# 6coils-1-discrete.net
KiCad netlist of a schematic drawn in EasyEDA
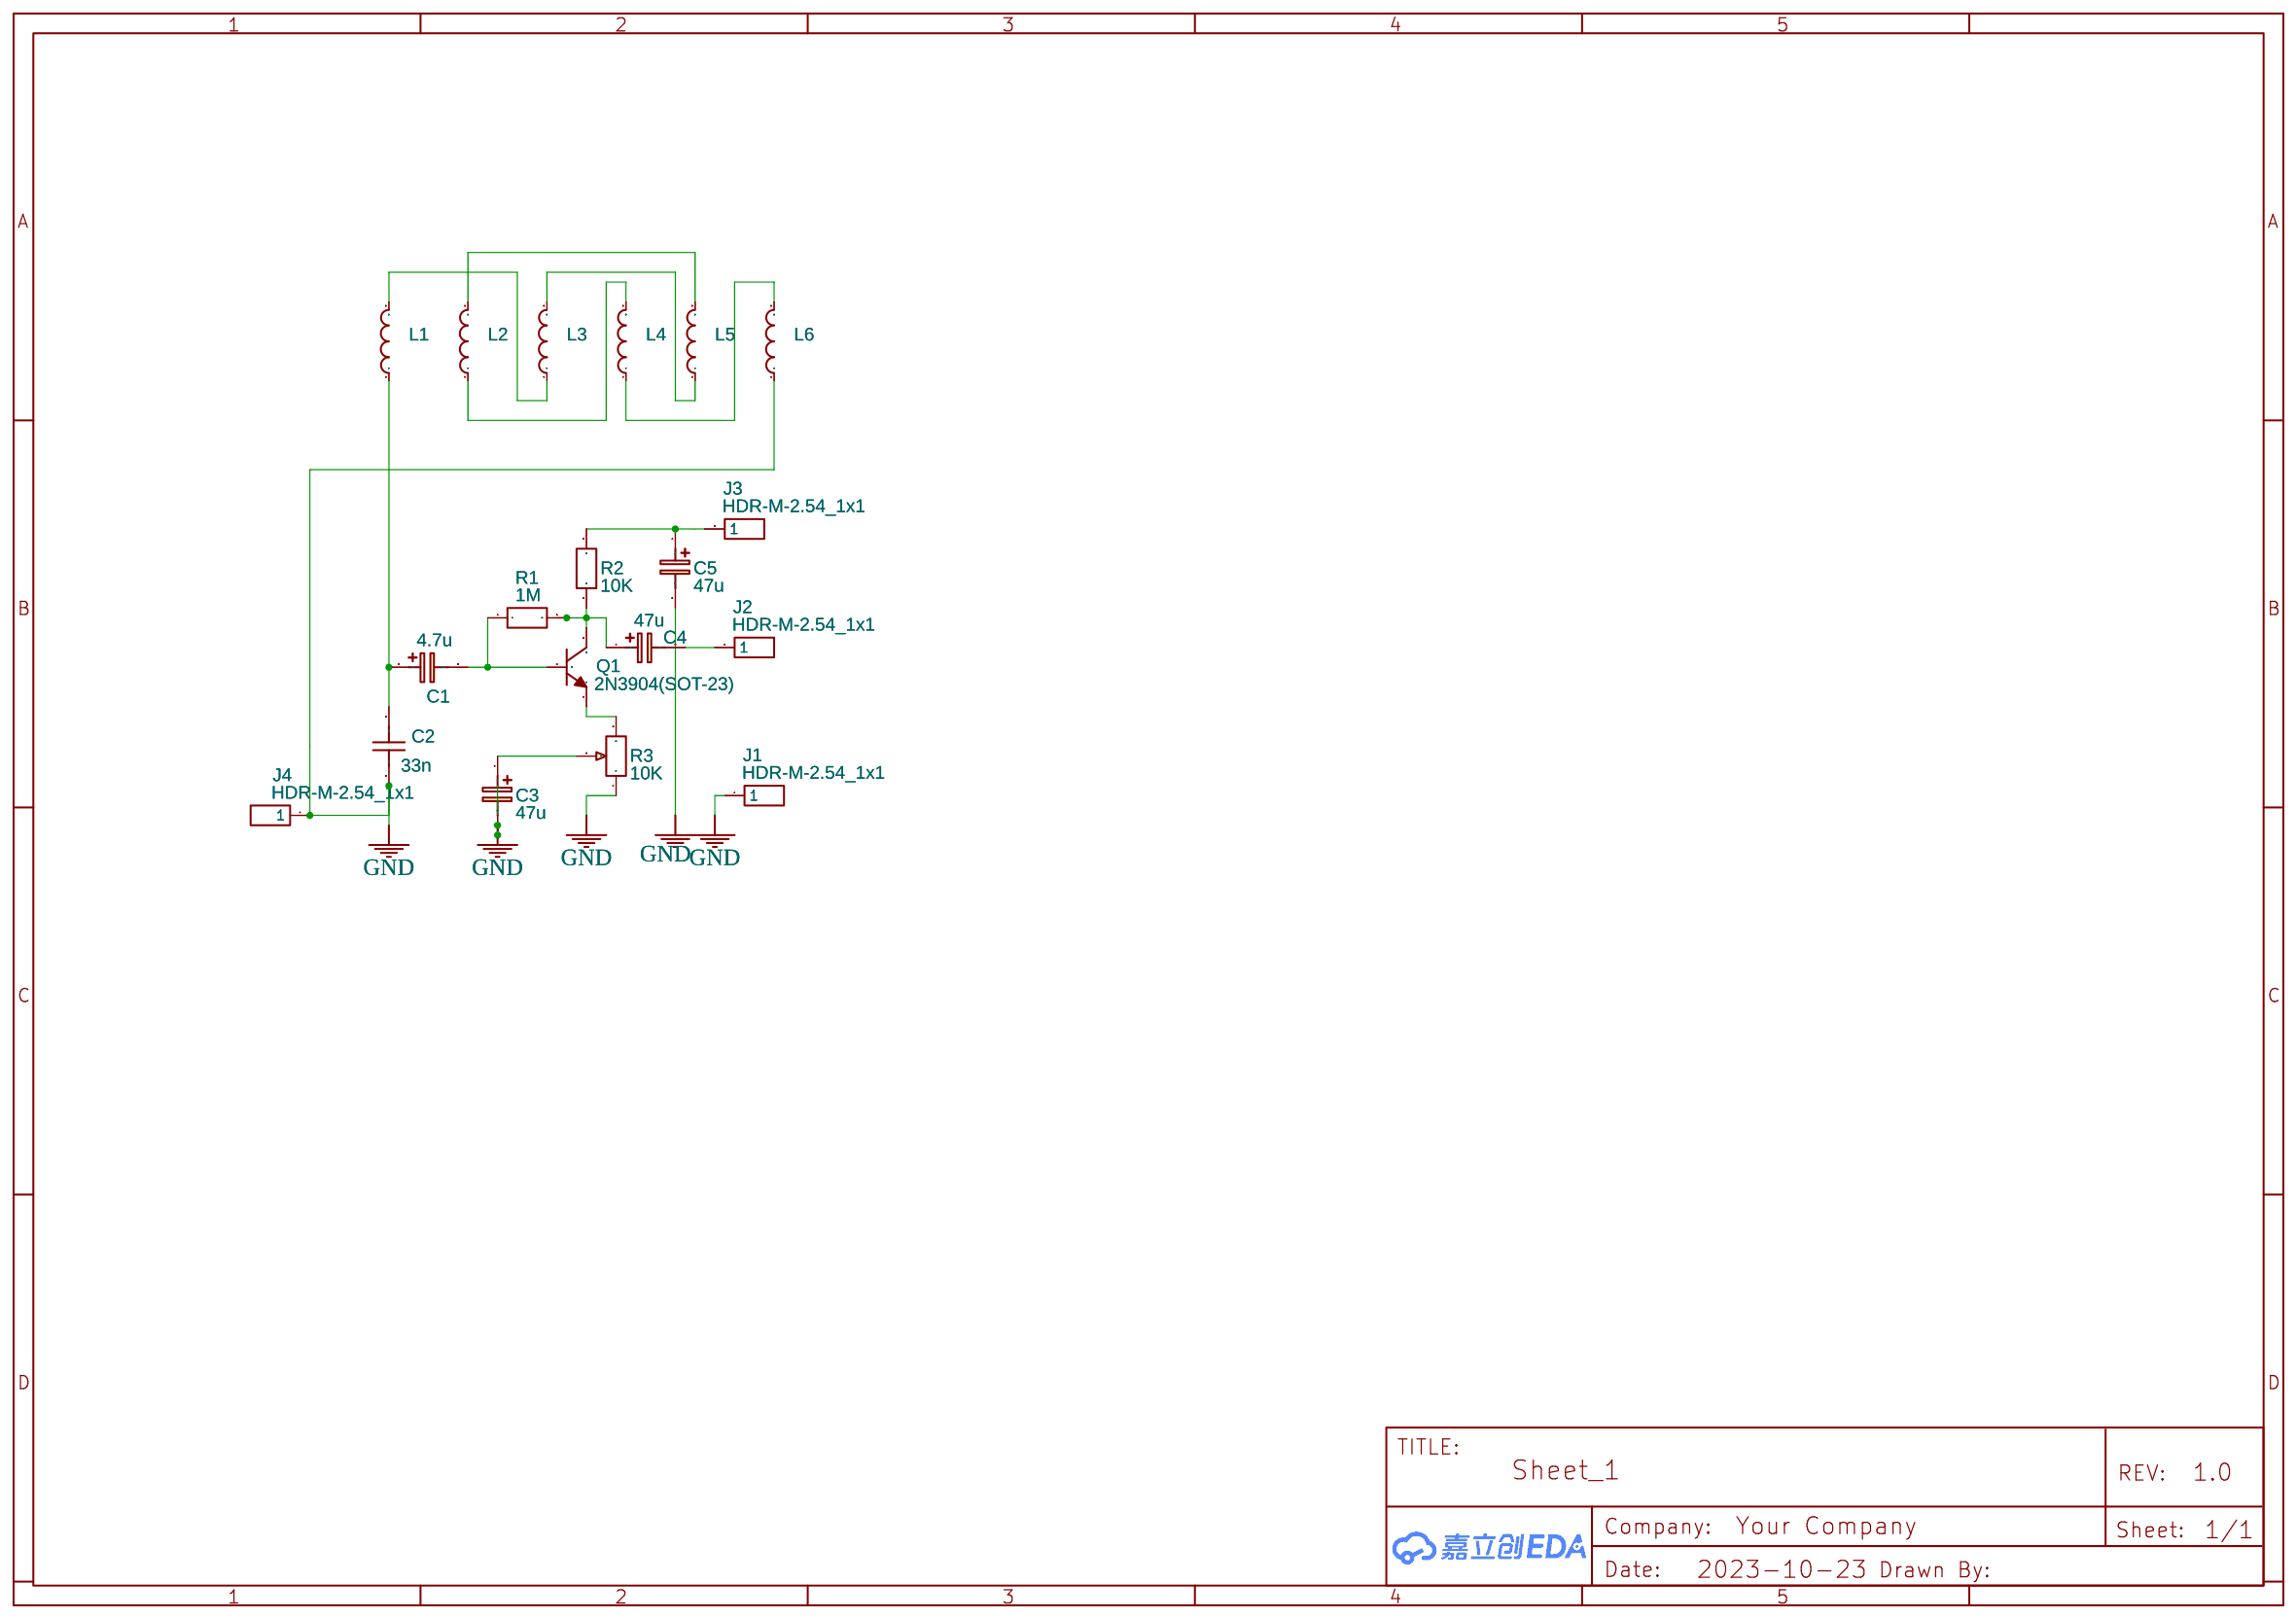
[diagram p0: schematic sheet]

(export (version "E")
  (design (tool "Eeschema 10.0.6"))
  (components
    (comp (ref "C1") (value "4.7u") (libsource (lib "") (part "C_Tan_SMD_A_EU_3")))
    (comp (ref "C2") (value "33n") (libsource (lib "") (part "C_0603_US")))
    (comp (ref "C3") (value "47u") (libsource (lib "") (part "C_Tan_SMD_A_EU_2")))
    (comp (ref "C4") (value "47u") (libsource (lib "") (part "C_Tan_SMD_A_EU")))
    (comp (ref "C5") (value "47u") (libsource (lib "") (part "C_Tan_SMD_A_EU_1")))
    (comp (ref "J1")
      (value "HDR-M-2.54_1x1")
      (fields (field (name "BOM_Supplier Part") "C81276"))
      (libsource (lib "") (part "HDR-M-2.54_1x1"))
    )
    (comp (ref "J2")
      (value "HDR-M-2.54_1x1")
      (fields (field (name "BOM_Supplier Part") "C81276"))
      (libsource (lib "") (part "HDR-M-2.54_1x1"))
    )
    (comp (ref "J3")
      (value "HDR-M-2.54_1x1")
      (fields (field (name "BOM_Supplier Part") "C81276"))
      (libsource (lib "") (part "HDR-M-2.54_1x1"))
    )
    (comp (ref "J4")
      (value "HDR-M-2.54_1x1")
      (fields (field (name "BOM_Supplier Part") "C81276"))
      (libsource (lib "") (part "HDR-M-2.54_1x1_1"))
    )
    (comp (ref "L1")
      (value "INDUCTOR_SMD:L_COILCRAFT_XXL4040")
      (fields (field (name "Manufacturer Part") "Inductor_SMD:L_Coilcraft_XxL4040"))
      (libsource (lib "") (part "INDUCTOR_SMD{colon}L_COILCRAFT_XXL4040"))
    )
    (comp (ref "L2")
      (value "INDUCTOR_SMD:L_COILCRAFT_XXL4040")
      (fields (field (name "Manufacturer Part") "Inductor_SMD:L_Coilcraft_XxL4040"))
      (libsource (lib "") (part "INDUCTOR_SMD{colon}L_COILCRAFT_XXL4040"))
    )
    (comp (ref "L3")
      (value "INDUCTOR_SMD:L_COILCRAFT_XXL4040")
      (fields (field (name "Manufacturer Part") "Inductor_SMD:L_Coilcraft_XxL4040"))
      (libsource (lib "") (part "INDUCTOR_SMD{colon}L_COILCRAFT_XXL4040_1"))
    )
    (comp (ref "L4")
      (value "INDUCTOR_SMD:L_COILCRAFT_XXL4040")
      (fields (field (name "Manufacturer Part") "Inductor_SMD:L_Coilcraft_XxL4040"))
      (libsource (lib "") (part "INDUCTOR_SMD{colon}L_COILCRAFT_XXL4040_1"))
    )
    (comp (ref "L5")
      (value "INDUCTOR_SMD:L_COILCRAFT_XXL4040")
      (fields (field (name "Manufacturer Part") "Inductor_SMD:L_Coilcraft_XxL4040"))
      (libsource (lib "") (part "INDUCTOR_SMD{colon}L_COILCRAFT_XXL4040_1"))
    )
    (comp (ref "L6")
      (value "INDUCTOR_SMD:L_COILCRAFT_XXL4040")
      (fields (field (name "Manufacturer Part") "Inductor_SMD:L_Coilcraft_XxL4040"))
      (libsource (lib "") (part "INDUCTOR_SMD{colon}L_COILCRAFT_XXL4040_1"))
    )
    (comp (ref "Q1")
      (value "2N3904(SOT-23)")
      (fields
        (field (name "BOM_Manufacturer Part") "2n3904S-RTK/PS")
        (field (name "BOM_Supplier Part") "C18536")
      )
      (libsource (lib "") (part "2N3904(SOT-23)"))
    )
    (comp (ref "R1") (value "1M") (libsource (lib "") (part "R_0603_EU")))
    (comp (ref "R2") (value "10K") (libsource (lib "") (part "R_0603_EU_1")))
    (comp (ref "R3")
      (value "10K")
      (fields (field (name "Manufacturer Part") "RM063-103 10K") (field (name "Manufacturer") "JML"))
      (libsource (lib "") (part "RM063-103 10K"))
    )
  )
  (nets
    (net (code "1") (name "GND") (class "Default")
      (node (ref "C2") (pin "1") (pinfunction "1_1") (pintype "unspecified"))
      (node (ref "C3") (pin "2") (pinfunction "2_2") (pintype "unspecified"))
      (node (ref "C5") (pin "2") (pinfunction "2_2") (pintype "unspecified"))
      (node (ref "J1") (pin "1") (pinfunction "1_1") (pintype "input"))
      (node (ref "J4") (pin "1") (pinfunction "1_1") (pintype "input"))
      (node (ref "L6") (pin "1") (pinfunction "1_1") (pintype "unspecified"))
      (node (ref "R3") (pin "1") (pinfunction "1_1") (pintype "input"))
    )
    (net (code "2") (name "Net-(C1-Pad1)") (class "Default")
      (node (ref "C1") (pin "1") (pinfunction "1_1") (pintype "unspecified"))
      (node (ref "C2") (pin "2") (pinfunction "2_2") (pintype "unspecified"))
      (node (ref "L1") (pin "1") (pinfunction "1_1") (pintype "unspecified"))
    )
    (net (code "3") (name "Net-(C3-Pad1)") (class "Default")
      (node (ref "C3") (pin "1") (pinfunction "1_1") (pintype "unspecified"))
      (node (ref "R3") (pin "2") (pinfunction "2_2") (pintype "input"))
    )
    (net (code "4") (name "Net-(C4-Pad2)") (class "Default")
      (node (ref "C4") (pin "2") (pinfunction "2_2") (pintype "unspecified"))
      (node (ref "J2") (pin "1") (pinfunction "1_1") (pintype "input"))
    )
    (net (code "5") (name "Net-(C5-Pad1)") (class "Default")
      (node (ref "C5") (pin "1") (pinfunction "1_1") (pintype "unspecified"))
      (node (ref "J3") (pin "1") (pinfunction "1_1") (pintype "input"))
      (node (ref "R2") (pin "2") (pinfunction "2_2") (pintype "unspecified"))
    )
    (net (code "6") (name "Net-(L1-Pad2)") (class "Default")
      (node (ref "L1") (pin "2") (pinfunction "2_2") (pintype "unspecified"))
      (node (ref "L3") (pin "1") (pinfunction "1_1") (pintype "unspecified"))
    )
    (net (code "7") (name "Net-(L2-Pad1)") (class "Default")
      (node (ref "L2") (pin "1") (pinfunction "1_1") (pintype "unspecified"))
      (node (ref "L4") (pin "2") (pinfunction "2_2") (pintype "unspecified"))
    )
    (net (code "8") (name "Net-(L2-Pad2)") (class "Default")
      (node (ref "L2") (pin "2") (pinfunction "2_2") (pintype "unspecified"))
      (node (ref "L5") (pin "2") (pinfunction "2_2") (pintype "unspecified"))
    )
    (net (code "9") (name "Net-(L3-Pad2)") (class "Default")
      (node (ref "L3") (pin "2") (pinfunction "2_2") (pintype "unspecified"))
      (node (ref "L5") (pin "1") (pinfunction "1_1") (pintype "unspecified"))
    )
    (net (code "10") (name "Net-(L4-Pad1)") (class "Default")
      (node (ref "L4") (pin "1") (pinfunction "1_1") (pintype "unspecified"))
      (node (ref "L6") (pin "2") (pinfunction "2_2") (pintype "unspecified"))
    )
    (net (code "11") (name "Net-(Q1-B)") (class "Default")
      (node (ref "C1") (pin "2") (pinfunction "2_2") (pintype "unspecified"))
      (node (ref "Q1") (pin "2") (pinfunction "B_2") (pintype "input"))
      (node (ref "R1") (pin "1") (pinfunction "1_1") (pintype "unspecified"))
    )
    (net (code "12") (name "Net-(Q1-C)") (class "Default")
      (node (ref "C4") (pin "1") (pinfunction "1_1") (pintype "unspecified"))
      (node (ref "Q1") (pin "3") (pinfunction "C_3") (pintype "input"))
      (node (ref "R1") (pin "2") (pinfunction "2_2") (pintype "unspecified"))
      (node (ref "R2") (pin "1") (pinfunction "1_1") (pintype "unspecified"))
    )
    (net (code "13") (name "Net-(Q1-E)") (class "Default")
      (node (ref "Q1") (pin "1") (pinfunction "E_1") (pintype "input"))
      (node (ref "R3") (pin "3") (pinfunction "3_3") (pintype "input"))
    )
  )
)
